# mkr1010_envMonitor_schematic.net
KiCad netlist of a schematic drawn in EAGLE
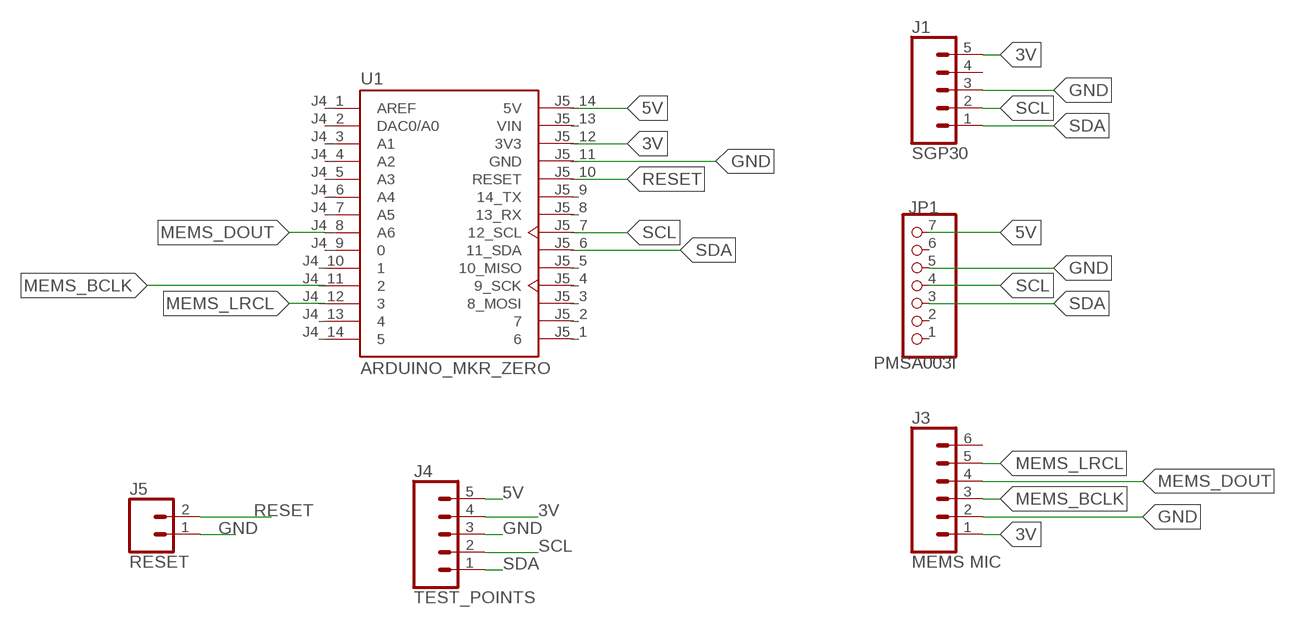
[diagram p0: schematic, sheet 1]

(export (version "E")
  (design (tool "Eeschema 10.0.6"))
  (components
    (comp (ref "J1")
      (value "SGP30")
      (footprint "eagle-import:1X05")
      (libsource (lib "eagle-import") (part "CONN_05"))
    )
    (comp (ref "J3")
      (value "MEMS MIC")
      (footprint "eagle-import:1X06")
      (libsource (lib "eagle-import") (part "CONN_06SILK_FEMALE_PTH"))
    )
    (comp (ref "J4")
      (value "TEST_POINTS")
      (footprint "eagle-import:1X05")
      (libsource (lib "eagle-import") (part "CONN_05"))
    )
    (comp (ref "J5")
      (value "RESET")
      (footprint "eagle-import:1X02")
      (libsource (lib "eagle-import") (part "CONN_02"))
    )
    (comp (ref "JP1")
      (value "PMSA003I")
      (footprint "eagle-import:1X07")
      (libsource (lib "eagle-import") (part "PINHD-1X7"))
    )
    (comp (ref "U1")
      (value "ARDUINO_MKR_ZERO")
      (footprint "eagle-import:MODULE_ARDUINO_MKR_ZERO")
      (fields (field (name "MF") "Arduino") (field (name "MP") "ARDUINO MKR ZERO"))
      (libsource (lib "eagle-import") (part "ARDUINO_MKR_ZERO"))
    )
  )
  (nets
    (net (code "1") (name "/VIN") (class "Default")
      (node (ref "U1") (pin "J5_13") (pinfunction "VIN_J5_13") (pintype "power_in"))
    )
    (net (code "2") (name "3V") (class "Default")
      (node (ref "J1") (pin "5") (pinfunction "5_5") (pintype "passive"))
      (node (ref "J3") (pin "1") (pinfunction "1_1") (pintype "passive"))
      (node (ref "J4") (pin "4") (pinfunction "4_4") (pintype "passive"))
      (node (ref "U1") (pin "J5_12") (pinfunction "3V3_J5_12") (pintype "power_in"))
    )
    (net (code "3") (name "5V") (class "Default")
      (node (ref "J4") (pin "5") (pinfunction "5_5") (pintype "passive"))
      (node (ref "JP1") (pin "7") (pinfunction "7_7") (pintype "passive"))
      (node (ref "U1") (pin "J5_14") (pinfunction "5V_J5_14") (pintype "power_in"))
    )
    (net (code "4") (name "GND") (class "Default")
      (node (ref "J1") (pin "3") (pinfunction "3_3") (pintype "passive"))
      (node (ref "J3") (pin "2") (pinfunction "2_2") (pintype "passive"))
      (node (ref "J4") (pin "3") (pinfunction "3_3") (pintype "passive"))
      (node (ref "J5") (pin "1") (pinfunction "1_1") (pintype "passive"))
      (node (ref "JP1") (pin "5") (pinfunction "5_5") (pintype "passive"))
      (node (ref "U1") (pin "J5_11") (pinfunction "GND_J5_11") (pintype "power_in"))
    )
    (net (code "5") (name "MEMS_BCLK") (class "Default")
      (node (ref "J3") (pin "3") (pinfunction "3_3") (pintype "passive"))
      (node (ref "U1") (pin "J4_11") (pinfunction "2_J4_11") (pintype "bidirectional"))
    )
    (net (code "6") (name "MEMS_DOUT") (class "Default")
      (node (ref "J3") (pin "4") (pinfunction "4_4") (pintype "passive"))
      (node (ref "U1") (pin "J4_8") (pinfunction "A6_J4_8") (pintype "bidirectional"))
    )
    (net (code "7") (name "MEMS_LRCL") (class "Default")
      (node (ref "J3") (pin "5") (pinfunction "5_5") (pintype "passive"))
      (node (ref "U1") (pin "J4_12") (pinfunction "3_J4_12") (pintype "bidirectional"))
    )
    (net (code "8") (name "RESET") (class "Default")
      (node (ref "J5") (pin "2") (pinfunction "2_2") (pintype "passive"))
      (node (ref "U1") (pin "J5_10") (pinfunction "RESET_J5_10") (pintype "bidirectional"))
    )
    (net (code "9") (name "SCL") (class "Default")
      (node (ref "J1") (pin "2") (pinfunction "2_2") (pintype "passive"))
      (node (ref "J4") (pin "2") (pinfunction "2_2") (pintype "passive"))
      (node (ref "JP1") (pin "4") (pinfunction "4_4") (pintype "passive"))
      (node (ref "U1") (pin "J5_7") (pinfunction "12_SCL_J5_7") (pintype "bidirectional"))
    )
    (net (code "10") (name "SDA") (class "Default")
      (node (ref "J1") (pin "1") (pinfunction "1_1") (pintype "passive"))
      (node (ref "J4") (pin "1") (pinfunction "1_1") (pintype "passive"))
      (node (ref "JP1") (pin "3") (pinfunction "3_3") (pintype "passive"))
      (node (ref "U1") (pin "J5_6") (pinfunction "11_SDA_J5_6") (pintype "bidirectional"))
    )
    (net (code "11") (name "unconnected-(J1-Pad4)") (class "Default")
      (node (ref "J1") (pin "4") (pinfunction "4_4") (pintype "passive"))
    )
    (net (code "12") (name "unconnected-(J3-Pad6)") (class "Default")
      (node (ref "J3") (pin "6") (pinfunction "6_6") (pintype "passive"))
    )
    (net (code "13") (name "unconnected-(JP1-Pad1)") (class "Default")
      (node (ref "JP1") (pin "1") (pinfunction "1_1") (pintype "passive"))
    )
    (net (code "14") (name "unconnected-(JP1-Pad2)") (class "Default")
      (node (ref "JP1") (pin "2") (pinfunction "2_2") (pintype "passive"))
    )
    (net (code "15") (name "unconnected-(JP1-Pad6)") (class "Default")
      (node (ref "JP1") (pin "6") (pinfunction "6_6") (pintype "passive"))
    )
    (net (code "16") (name "unconnected-(U1-0-PadJ4_9)") (class "Default")
      (node (ref "U1") (pin "J4_9") (pinfunction "0_J4_9") (pintype "bidirectional"))
    )
    (net (code "17") (name "unconnected-(U1-1-PadJ4_10)") (class "Default")
      (node (ref "U1") (pin "J4_10") (pinfunction "1_J4_10") (pintype "bidirectional"))
    )
    (net (code "18") (name "unconnected-(U1-4-PadJ4_13)") (class "Default")
      (node (ref "U1") (pin "J4_13") (pinfunction "4_J4_13") (pintype "bidirectional"))
    )
    (net (code "19") (name "unconnected-(U1-5-PadJ4_14)") (class "Default")
      (node (ref "U1") (pin "J4_14") (pinfunction "5_J4_14") (pintype "bidirectional"))
    )
    (net (code "20") (name "unconnected-(U1-6-PadJ5_1)") (class "Default")
      (node (ref "U1") (pin "J5_1") (pinfunction "6_J5_1") (pintype "bidirectional"))
    )
    (net (code "21") (name "unconnected-(U1-7-PadJ5_2)") (class "Default")
      (node (ref "U1") (pin "J5_2") (pinfunction "7_J5_2") (pintype "bidirectional"))
    )
    (net (code "22") (name "unconnected-(U1-8_MOSI-PadJ5_3)") (class "Default")
      (node (ref "U1") (pin "J5_3") (pinfunction "8_MOSI_J5_3") (pintype "bidirectional"))
    )
    (net (code "23") (name "unconnected-(U1-9_SCK-PadJ5_4)") (class "Default")
      (node (ref "U1") (pin "J5_4") (pinfunction "9_SCK_J5_4") (pintype "bidirectional"))
    )
    (net (code "24") (name "unconnected-(U1-10_MISO-PadJ5_5)") (class "Default")
      (node (ref "U1") (pin "J5_5") (pinfunction "10_MISO_J5_5") (pintype "bidirectional"))
    )
    (net (code "25") (name "unconnected-(U1-13_RX-PadJ5_8)") (class "Default")
      (node (ref "U1") (pin "J5_8") (pinfunction "13_RX_J5_8") (pintype "input"))
    )
    (net (code "26") (name "unconnected-(U1-14_TX-PadJ5_9)") (class "Default")
      (node (ref "U1") (pin "J5_9") (pinfunction "14_TX_J5_9") (pintype "output"))
    )
    (net (code "27") (name "unconnected-(U1-A1-PadJ4_3)") (class "Default")
      (node (ref "U1") (pin "J4_3") (pinfunction "A1_J4_3") (pintype "bidirectional"))
    )
    (net (code "28") (name "unconnected-(U1-A2-PadJ4_4)") (class "Default")
      (node (ref "U1") (pin "J4_4") (pinfunction "A2_J4_4") (pintype "bidirectional"))
    )
    (net (code "29") (name "unconnected-(U1-A3-PadJ4_5)") (class "Default")
      (node (ref "U1") (pin "J4_5") (pinfunction "A3_J4_5") (pintype "bidirectional"))
    )
    (net (code "30") (name "unconnected-(U1-A4-PadJ4_6)") (class "Default")
      (node (ref "U1") (pin "J4_6") (pinfunction "A4_J4_6") (pintype "bidirectional"))
    )
    (net (code "31") (name "unconnected-(U1-A5-PadJ4_7)") (class "Default")
      (node (ref "U1") (pin "J4_7") (pinfunction "A5_J4_7") (pintype "bidirectional"))
    )
    (net (code "32") (name "unconnected-(U1-AREF-PadJ4_1)") (class "Default")
      (node (ref "U1") (pin "J4_1") (pinfunction "AREF_J4_1") (pintype "bidirectional"))
    )
    (net (code "33") (name "unconnected-(U1-DAC0{slash}A0-PadJ4_2)") (class "Default")
      (node (ref "U1") (pin "J4_2") (pinfunction "DAC0/A0_J4_2") (pintype "bidirectional"))
    )
  )
)
